# open-access-interlock-v1-1.net
KiCad netlist of a schematic drawn in EAGLE
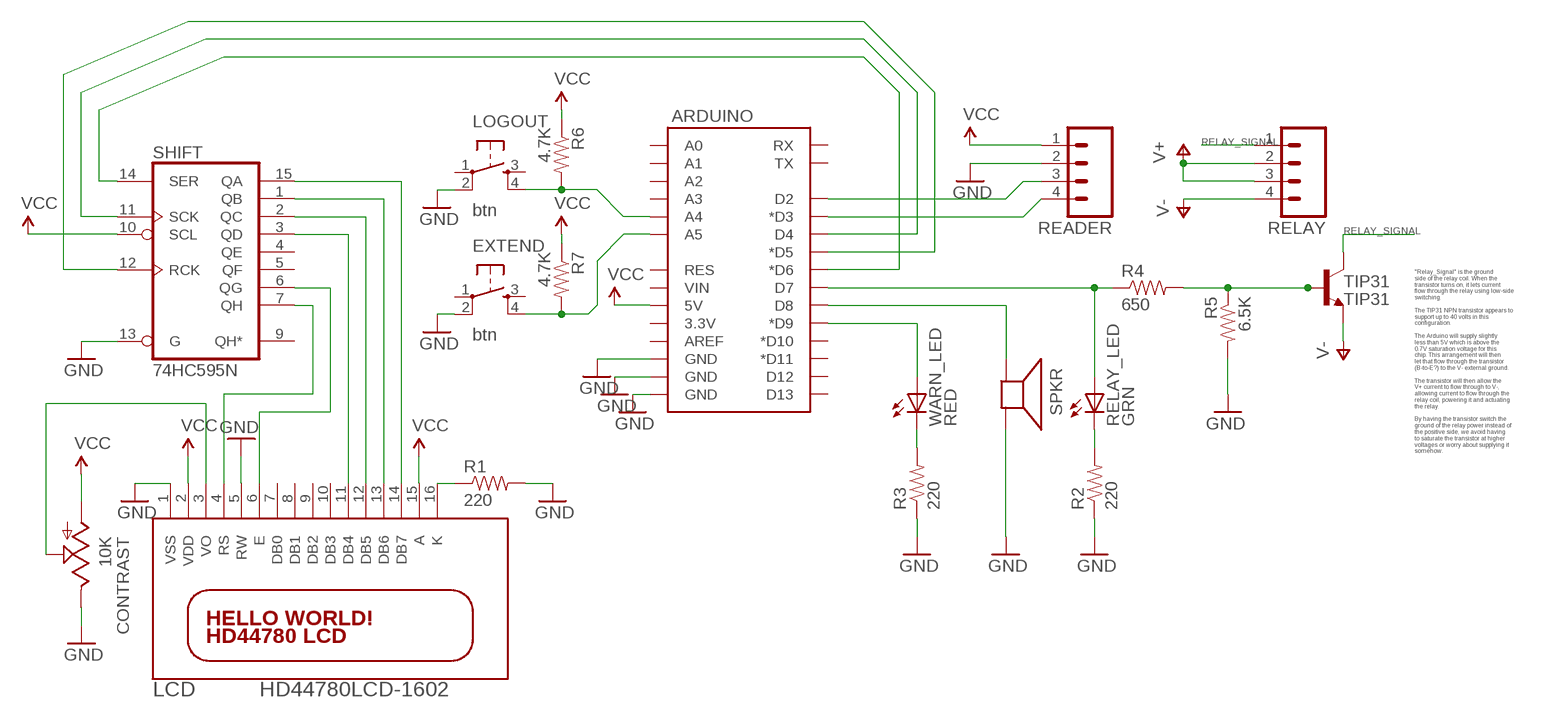
[diagram p0: schematic, sheet 1]

(export (version "E")
  (design (tool "Eeschema 10.0.6"))
  (components
    (comp (ref "ARDUINO")
      (value "ARDUINO_SHIELDNO_SILK")
      (footprint "eagle-import:DUEMILANOVE_VIAS")
      (libsource (lib "eagle-import") (part "ARDUINO_SHIELDNO_SILK"))
    )
    (comp (ref "CONTRAST")
      (value "10K")
      (footprint "eagle-import:RS3")
      (libsource (lib "eagle-import") (part "TRIM_US-RS3"))
    )
    (comp (ref "EXTEND")
      (value "btn")
      (footprint "eagle-import:TACTILE-PTH")
      (libsource (lib "eagle-import") (part "TAC_SWITCHPTH"))
    )
    (comp (ref "LCD")
      (value "HD44780LCD-1602")
      (footprint "eagle-import:LCD1602")
      (libsource (lib "eagle-import") (part "HD44780LCD-1602"))
    )
    (comp (ref "LOGOUT")
      (value "btn")
      (footprint "eagle-import:TACTILE-PTH")
      (libsource (lib "eagle-import") (part "TAC_SWITCHPTH"))
    )
    (comp (ref "R1")
      (value "220")
      (footprint "eagle-import:AXIAL-0.3")
      (libsource (lib "eagle-import") (part "RESISTORAXIAL-0.3"))
    )
    (comp (ref "R2")
      (value "220")
      (footprint "eagle-import:AXIAL-0.3")
      (libsource (lib "eagle-import") (part "RESISTORAXIAL-0.3"))
    )
    (comp (ref "R3")
      (value "220")
      (footprint "eagle-import:AXIAL-0.3")
      (libsource (lib "eagle-import") (part "RESISTORAXIAL-0.3"))
    )
    (comp (ref "R4")
      (value "650")
      (footprint "eagle-import:AXIAL-0.3")
      (libsource (lib "eagle-import") (part "RESISTORAXIAL-0.3"))
    )
    (comp (ref "R5")
      (value "6.5K")
      (footprint "eagle-import:AXIAL-0.3")
      (libsource (lib "eagle-import") (part "RESISTORAXIAL-0.3"))
    )
    (comp (ref "R6")
      (value "4.7K")
      (footprint "eagle-import:AXIAL-0.3")
      (libsource (lib "eagle-import") (part "RESISTORAXIAL-0.3"))
    )
    (comp (ref "R7")
      (value "4.7K")
      (footprint "eagle-import:AXIAL-0.3")
      (libsource (lib "eagle-import") (part "RESISTORAXIAL-0.3"))
    )
    (comp (ref "READER")
      (value "M04SCREW")
      (footprint "eagle-import:SCREWTERMINAL-3.5MM-4")
      (libsource (lib "eagle-import") (part "M04SCREW"))
    )
    (comp (ref "RELAY")
      (value "M04SCREW")
      (footprint "eagle-import:SCREWTERMINAL-3.5MM-4")
      (libsource (lib "eagle-import") (part "M04SCREW"))
    )
    (comp (ref "RELAY_LED")
      (value "GRN")
      (footprint "eagle-import:LED5MM")
      (libsource (lib "eagle-import") (part "LED5MM"))
    )
    (comp (ref "SHIFT")
      (value "74HC595N")
      (footprint "eagle-import:DIL16")
      (libsource (lib "eagle-import") (part "74595NHC"))
    )
    (comp (ref "SPKR")
      (value "SPEAKER/PS12")
      (footprint "eagle-import:PS12")
      (libsource (lib "eagle-import") (part "SPEAKER/PS12"))
    )
    (comp (ref "TIP31")
      (value "TIP31")
      (footprint "eagle-import:TO220")
      (libsource (lib "eagle-import") (part "TIP31"))
    )
    (comp (ref "WARN_LED")
      (value "RED")
      (footprint "eagle-import:LED5MM")
      (libsource (lib "eagle-import") (part "LED5MM"))
    )
  )
  (nets
    (net (code "1") (name "/RELAY_SIGNAL") (class "Default")
      (node (ref "RELAY") (pin "1") (pinfunction "1_1") (pintype "passive"))
      (node (ref "TIP31") (pin "2") (pinfunction "C_2") (pintype "passive"))
    )
    (net (code "2") (name "GND") (class "Default")
      (node (ref "ARDUINO") (pin "GND@0") (pinfunction "GND_GND@0") (pintype "bidirectional"))
      (node (ref "ARDUINO") (pin "GND@1") (pinfunction "GND_GND@1") (pintype "bidirectional"))
      (node (ref "ARDUINO") (pin "GND@2") (pinfunction "GND_GND@2") (pintype "bidirectional"))
      (node (ref "CONTRAST") (pin "E") (pinfunction "E_E") (pintype "passive"))
      (node (ref "EXTEND") (pin "2") (pinfunction "2_2") (pintype "passive"))
      (node (ref "LCD") (pin "1") (pinfunction "VSS_1") (pintype "power_in"))
      (node (ref "LCD") (pin "5") (pinfunction "RW_5") (pintype "input"))
      (node (ref "LOGOUT") (pin "2") (pinfunction "2_2") (pintype "passive"))
      (node (ref "R1") (pin "P$2") (pinfunction "2_P$2") (pintype "passive"))
      (node (ref "R2") (pin "P$1") (pinfunction "1_P$1") (pintype "passive"))
      (node (ref "R3") (pin "P$1") (pinfunction "1_P$1") (pintype "passive"))
      (node (ref "R5") (pin "P$2") (pinfunction "2_P$2") (pintype "passive"))
      (node (ref "READER") (pin "2") (pinfunction "2_2") (pintype "passive"))
      (node (ref "SHIFT") (pin "13") (pinfunction "G_13") (pintype "input"))
      (node (ref "SPKR") (pin "P$2") (pinfunction "-_P$2") (pintype "passive"))
    )
    (net (code "3") (name "Net-(ARDUINO-*D3)") (class "Default")
      (node (ref "ARDUINO") (pin "D3") (pinfunction "*D3_D3") (pintype "bidirectional"))
      (node (ref "READER") (pin "4") (pinfunction "4_4") (pintype "passive"))
    )
    (net (code "4") (name "Net-(ARDUINO-*D5)") (class "Default")
      (node (ref "ARDUINO") (pin "D5") (pinfunction "*D5_D5") (pintype "bidirectional"))
      (node (ref "SHIFT") (pin "12") (pinfunction "RCK_12") (pintype "input"))
    )
    (net (code "5") (name "Net-(ARDUINO-*D6)") (class "Default")
      (node (ref "ARDUINO") (pin "D6") (pinfunction "*D6_D6") (pintype "bidirectional"))
      (node (ref "SHIFT") (pin "14") (pinfunction "SER_14") (pintype "input"))
    )
    (net (code "6") (name "Net-(ARDUINO-*D9)") (class "Default")
      (node (ref "ARDUINO") (pin "D9") (pinfunction "*D9_D9") (pintype "bidirectional"))
      (node (ref "WARN_LED") (pin "A") (pinfunction "A_A") (pintype "passive"))
    )
    (net (code "7") (name "Net-(ARDUINO-PadD2)") (class "Default")
      (node (ref "ARDUINO") (pin "D2") (pinfunction "D2_D2") (pintype "bidirectional"))
      (node (ref "READER") (pin "3") (pinfunction "3_3") (pintype "passive"))
    )
    (net (code "8") (name "Net-(LCD-DB4)") (class "Default")
      (node (ref "LCD") (pin "11") (pinfunction "DB4_11") (pintype "bidirectional"))
      (node (ref "SHIFT") (pin "3") (pinfunction "QD_3") (pintype "tri_state"))
    )
    (net (code "9") (name "Net-(LCD-DB5)") (class "Default")
      (node (ref "LCD") (pin "12") (pinfunction "DB5_12") (pintype "bidirectional"))
      (node (ref "SHIFT") (pin "2") (pinfunction "QC_2") (pintype "tri_state"))
    )
    (net (code "10") (name "Net-(LCD-DB6)") (class "Default")
      (node (ref "LCD") (pin "13") (pinfunction "DB6_13") (pintype "bidirectional"))
      (node (ref "SHIFT") (pin "1") (pinfunction "QB_1") (pintype "tri_state"))
    )
    (net (code "11") (name "Net-(LCD-DB7)") (class "Default")
      (node (ref "LCD") (pin "14") (pinfunction "DB7_14") (pintype "bidirectional"))
      (node (ref "SHIFT") (pin "15") (pinfunction "QA_15") (pintype "tri_state"))
    )
    (net (code "12") (name "Net-(LCD-E)") (class "Default")
      (node (ref "LCD") (pin "6") (pinfunction "E_6") (pintype "input"))
      (node (ref "SHIFT") (pin "6") (pinfunction "QG_6") (pintype "tri_state"))
    )
    (net (code "13") (name "Net-(LCD-K)") (class "Default")
      (node (ref "LCD") (pin "16") (pinfunction "K_16") (pintype "input"))
      (node (ref "R1") (pin "P$1") (pinfunction "1_P$1") (pintype "passive"))
    )
    (net (code "14") (name "Net-(LCD-RS)") (class "Default")
      (node (ref "LCD") (pin "4") (pinfunction "RS_4") (pintype "input"))
      (node (ref "SHIFT") (pin "7") (pinfunction "QH_7") (pintype "tri_state"))
    )
    (net (code "15") (name "Net-(LCD-VO)") (class "Default")
      (node (ref "CONTRAST") (pin "S") (pinfunction "S_S") (pintype "passive"))
      (node (ref "LCD") (pin "3") (pinfunction "VO_3") (pintype "input"))
    )
    (net (code "16") (name "Net-(R2-2)") (class "Default")
      (node (ref "R2") (pin "P$2") (pinfunction "2_P$2") (pintype "passive"))
      (node (ref "RELAY_LED") (pin "K") (pinfunction "C_K") (pintype "passive"))
    )
    (net (code "17") (name "Net-(R3-2)") (class "Default")
      (node (ref "R3") (pin "P$2") (pinfunction "2_P$2") (pintype "passive"))
      (node (ref "WARN_LED") (pin "K") (pinfunction "C_K") (pintype "passive"))
    )
    (net (code "18") (name "Net-(R4-1)") (class "Default")
      (node (ref "ARDUINO") (pin "D7") (pinfunction "D7_D7") (pintype "bidirectional"))
      (node (ref "R4") (pin "P$1") (pinfunction "1_P$1") (pintype "passive"))
      (node (ref "RELAY_LED") (pin "A") (pinfunction "A_A") (pintype "passive"))
    )
    (net (code "19") (name "Net-(R4-2)") (class "Default")
      (node (ref "R4") (pin "P$2") (pinfunction "2_P$2") (pintype "passive"))
      (node (ref "R5") (pin "P$1") (pinfunction "1_P$1") (pintype "passive"))
      (node (ref "TIP31") (pin "1") (pinfunction "B_1") (pintype "passive"))
    )
    (net (code "20") (name "Net-(R6-2)") (class "Default")
      (node (ref "ARDUINO") (pin "A4") (pinfunction "A4_A4") (pintype "bidirectional"))
      (node (ref "LOGOUT") (pin "4") (pinfunction "4_4") (pintype "passive"))
      (node (ref "R6") (pin "P$2") (pinfunction "2_P$2") (pintype "passive"))
    )
    (net (code "21") (name "Net-(R7-2)") (class "Default")
      (node (ref "ARDUINO") (pin "A5") (pinfunction "A5_A5") (pintype "bidirectional"))
      (node (ref "EXTEND") (pin "4") (pinfunction "4_4") (pintype "passive"))
      (node (ref "R7") (pin "P$2") (pinfunction "2_P$2") (pintype "passive"))
    )
    (net (code "22") (name "Net-(SHIFTA-SCK)") (class "Default")
      (node (ref "ARDUINO") (pin "D4") (pinfunction "D4_D4") (pintype "bidirectional"))
      (node (ref "SHIFT") (pin "11") (pinfunction "SCK_11") (pintype "input"))
    )
    (net (code "23") (name "Net-(SPKR-+)") (class "Default")
      (node (ref "ARDUINO") (pin "D8") (pinfunction "D8_D8") (pintype "bidirectional"))
      (node (ref "SPKR") (pin "P$1") (pinfunction "+_P$1") (pintype "passive"))
    )
    (net (code "24") (name "V+") (class "Default")
      (node (ref "RELAY") (pin "2") (pinfunction "2_2") (pintype "passive"))
      (node (ref "RELAY") (pin "3") (pinfunction "3_3") (pintype "passive"))
    )
    (net (code "25") (name "V-") (class "Default")
      (node (ref "RELAY") (pin "4") (pinfunction "4_4") (pintype "passive"))
      (node (ref "TIP31") (pin "3") (pinfunction "E_3") (pintype "passive"))
    )
    (net (code "26") (name "VCC") (class "Default")
      (node (ref "ARDUINO") (pin "5V") (pinfunction "5V_5V") (pintype "bidirectional"))
      (node (ref "CONTRAST") (pin "A") (pinfunction "A_A") (pintype "passive"))
      (node (ref "LCD") (pin "15") (pinfunction "A_15") (pintype "input"))
      (node (ref "LCD") (pin "2") (pinfunction "VDD_2") (pintype "power_in"))
      (node (ref "R6") (pin "P$1") (pinfunction "1_P$1") (pintype "passive"))
      (node (ref "R7") (pin "P$1") (pinfunction "1_P$1") (pintype "passive"))
      (node (ref "READER") (pin "1") (pinfunction "1_1") (pintype "passive"))
      (node (ref "SHIFT") (pin "10") (pinfunction "SCL_10") (pintype "input"))
    )
    (net (code "27") (name "unconnected-(ARDUINO-*D10-PadD10)") (class "Default")
      (node (ref "ARDUINO") (pin "D10") (pinfunction "*D10_D10") (pintype "bidirectional"))
    )
    (net (code "28") (name "unconnected-(ARDUINO-*D11-PadD11)") (class "Default")
      (node (ref "ARDUINO") (pin "D11") (pinfunction "*D11_D11") (pintype "bidirectional"))
    )
    (net (code "29") (name "unconnected-(ARDUINO-Pad3.3V)") (class "Default")
      (node (ref "ARDUINO") (pin "3.3V") (pinfunction "3.3V_3.3V") (pintype "bidirectional"))
    )
    (net (code "30") (name "unconnected-(ARDUINO-PadA0)") (class "Default")
      (node (ref "ARDUINO") (pin "A0") (pinfunction "A0_A0") (pintype "bidirectional"))
    )
    (net (code "31") (name "unconnected-(ARDUINO-PadA1)") (class "Default")
      (node (ref "ARDUINO") (pin "A1") (pinfunction "A1_A1") (pintype "bidirectional"))
    )
    (net (code "32") (name "unconnected-(ARDUINO-PadA2)") (class "Default")
      (node (ref "ARDUINO") (pin "A2") (pinfunction "A2_A2") (pintype "bidirectional"))
    )
    (net (code "33") (name "unconnected-(ARDUINO-PadA3)") (class "Default")
      (node (ref "ARDUINO") (pin "A3") (pinfunction "A3_A3") (pintype "bidirectional"))
    )
    (net (code "34") (name "unconnected-(ARDUINO-PadAREF)") (class "Default")
      (node (ref "ARDUINO") (pin "AREF") (pinfunction "AREF_AREF") (pintype "bidirectional"))
    )
    (net (code "35") (name "unconnected-(ARDUINO-PadD12)") (class "Default")
      (node (ref "ARDUINO") (pin "D12") (pinfunction "D12_D12") (pintype "bidirectional"))
    )
    (net (code "36") (name "unconnected-(ARDUINO-PadD13)") (class "Default")
      (node (ref "ARDUINO") (pin "D13") (pinfunction "D13_D13") (pintype "bidirectional"))
    )
    (net (code "37") (name "unconnected-(ARDUINO-PadRES)") (class "Default")
      (node (ref "ARDUINO") (pin "RES") (pinfunction "RES_RES") (pintype "bidirectional"))
    )
    (net (code "38") (name "unconnected-(ARDUINO-PadRX)") (class "Default")
      (node (ref "ARDUINO") (pin "RX") (pinfunction "RX_RX") (pintype "bidirectional"))
    )
    (net (code "39") (name "unconnected-(ARDUINO-PadTX)") (class "Default")
      (node (ref "ARDUINO") (pin "TX") (pinfunction "TX_TX") (pintype "bidirectional"))
    )
    (net (code "40") (name "unconnected-(ARDUINO-PadVIN)") (class "Default")
      (node (ref "ARDUINO") (pin "VIN") (pinfunction "VIN_VIN") (pintype "bidirectional"))
    )
    (net (code "41") (name "unconnected-(EXTEND-Pad1)") (class "Default")
      (node (ref "EXTEND") (pin "1") (pinfunction "1_1") (pintype "passive"))
    )
    (net (code "42") (name "unconnected-(EXTEND-Pad3)") (class "Default")
      (node (ref "EXTEND") (pin "3") (pinfunction "3_3") (pintype "passive"))
    )
    (net (code "43") (name "unconnected-(LCD-DB0-Pad7)") (class "Default")
      (node (ref "LCD") (pin "7") (pinfunction "DB0_7") (pintype "bidirectional"))
    )
    (net (code "44") (name "unconnected-(LCD-DB1-Pad8)") (class "Default")
      (node (ref "LCD") (pin "8") (pinfunction "DB1_8") (pintype "bidirectional"))
    )
    (net (code "45") (name "unconnected-(LCD-DB2-Pad9)") (class "Default")
      (node (ref "LCD") (pin "9") (pinfunction "DB2_9") (pintype "bidirectional"))
    )
    (net (code "46") (name "unconnected-(LCD-DB3-Pad10)") (class "Default")
      (node (ref "LCD") (pin "10") (pinfunction "DB3_10") (pintype "bidirectional"))
    )
    (net (code "47") (name "unconnected-(LOGOUT-Pad1)") (class "Default")
      (node (ref "LOGOUT") (pin "1") (pinfunction "1_1") (pintype "passive"))
    )
    (net (code "48") (name "unconnected-(LOGOUT-Pad3)") (class "Default")
      (node (ref "LOGOUT") (pin "3") (pinfunction "3_3") (pintype "passive"))
    )
    (net (code "49") (name "unconnected-(SHIFTA-QE-Pad4)") (class "Default")
      (node (ref "SHIFT") (pin "4") (pinfunction "QE_4") (pintype "tri_state"))
    )
    (net (code "50") (name "unconnected-(SHIFTA-QF-Pad5)") (class "Default")
      (node (ref "SHIFT") (pin "5") (pinfunction "QF_5") (pintype "tri_state"))
    )
    (net (code "51") (name "unconnected-(SHIFTA-QH*-Pad9)") (class "Default")
      (node (ref "SHIFT") (pin "9") (pinfunction "QH*_9") (pintype "tri_state"))
    )
  )
)
